# Decoder.net
KiCad netlist of a schematic drawn in EAGLE
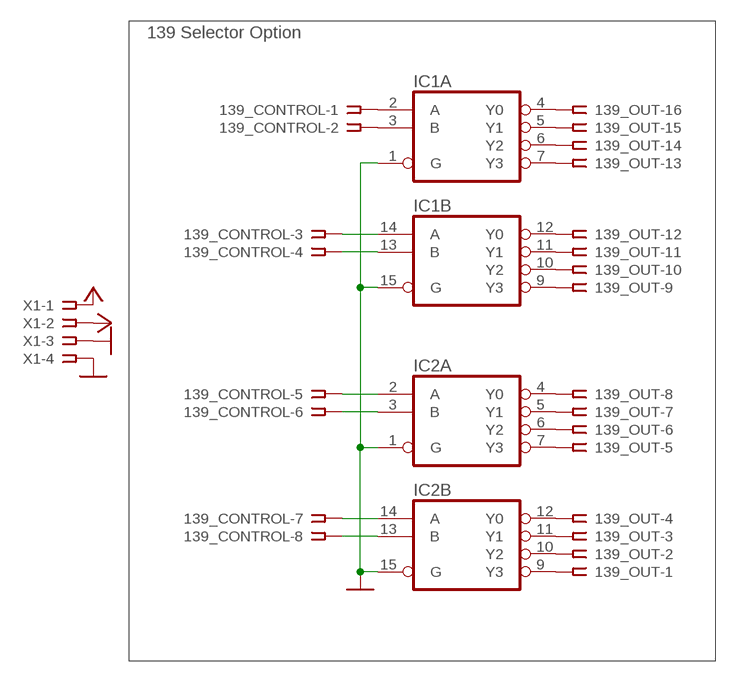
[diagram p0: schematic, sheet 1]

(export (version "E")
  (design (tool "Eeschema 10.0.6"))
  (components
    (comp (ref "139_CONTROL")
      (value "SSW-108-02-G-S")
      (footprint "eagle-import:SSW-108-02-G-S")
      (fields (field (name "MF") "Samtec Inc."))
      (libsource (lib "eagle-import") (part "SSW-108-02-G-S"))
    )
    (comp (ref "139_OUT")
      (value "SSW-116-02-G-S")
      (footprint "eagle-import:SSW-116-02-G-S")
      (fields (field (name "MF") "Samtec Inc."))
      (libsource (lib "eagle-import") (part "SSW-116-02-G-S"))
    )
    (comp (ref "IC1")
      (value "74AC139N")
      (footprint "eagle-import:DIL16")
      (libsource (lib "eagle-import") (part "74139NAC"))
    )
    (comp (ref "IC2")
      (value "74AC139N")
      (footprint "eagle-import:DIL16")
      (libsource (lib "eagle-import") (part "74139NAC"))
    )
    (comp (ref "X1")
      (value "SSW-104-02-G-S")
      (footprint "eagle-import:SSW-104-02-G-S")
      (fields (field (name "MF") "Samtec Inc."))
      (libsource (lib "eagle-import") (part "SSW-104-02-G-S"))
    )
  )
  (nets
    (net (code "1") (name "GND") (class "Default")
      (node (ref "IC1") (pin "1") (pinfunction "G_1") (pintype "input"))
      (node (ref "IC1") (pin "15") (pinfunction "G_15") (pintype "input"))
      (node (ref "IC2") (pin "1") (pinfunction "G_1") (pintype "input"))
      (node (ref "IC2") (pin "15") (pinfunction "G_15") (pintype "input"))
      (node (ref "X1") (pin "3") (pinfunction "1_3") (pintype "passive"))
      (node (ref "X1") (pin "4") (pinfunction "1_4") (pintype "passive"))
    )
    (net (code "2") (name "Net-(139_CONTROLB-1)") (class "Default")
      (node (ref "139_CONTROL") (pin "2") (pinfunction "1_2") (pintype "passive"))
      (node (ref "IC1") (pin "3") (pinfunction "B_3") (pintype "input"))
    )
    (net (code "3") (name "Net-(139_CONTROLC-1)") (class "Default")
      (node (ref "139_CONTROL") (pin "3") (pinfunction "1_3") (pintype "passive"))
      (node (ref "IC1") (pin "14") (pinfunction "A_14") (pintype "input"))
    )
    (net (code "4") (name "Net-(139_CONTROLD-1)") (class "Default")
      (node (ref "139_CONTROL") (pin "4") (pinfunction "1_4") (pintype "passive"))
      (node (ref "IC1") (pin "13") (pinfunction "B_13") (pintype "input"))
    )
    (net (code "5") (name "Net-(139_CONTROLE-1)") (class "Default")
      (node (ref "139_CONTROL") (pin "5") (pinfunction "1_5") (pintype "passive"))
      (node (ref "IC2") (pin "2") (pinfunction "A_2") (pintype "input"))
    )
    (net (code "6") (name "Net-(139_CONTROLF-1)") (class "Default")
      (node (ref "139_CONTROL") (pin "6") (pinfunction "1_6") (pintype "passive"))
      (node (ref "IC2") (pin "3") (pinfunction "B_3") (pintype "input"))
    )
    (net (code "7") (name "Net-(139_CONTROLG-1)") (class "Default")
      (node (ref "139_CONTROL") (pin "7") (pinfunction "1_7") (pintype "passive"))
      (node (ref "IC2") (pin "14") (pinfunction "A_14") (pintype "input"))
    )
    (net (code "8") (name "Net-(139_CONTROLH-1)") (class "Default")
      (node (ref "139_CONTROL") (pin "8") (pinfunction "1_8") (pintype "passive"))
      (node (ref "IC2") (pin "13") (pinfunction "B_13") (pintype "input"))
    )
    (net (code "9") (name "Net-(139_OUTB-1)") (class "Default")
      (node (ref "139_OUT") (pin "10") (pinfunction "1_10") (pintype "passive"))
      (node (ref "IC1") (pin "10") (pinfunction "Y2_10") (pintype "output"))
    )
    (net (code "10") (name "Net-(139_OUTC-1)") (class "Default")
      (node (ref "139_OUT") (pin "11") (pinfunction "1_11") (pintype "passive"))
      (node (ref "IC1") (pin "11") (pinfunction "Y1_11") (pintype "output"))
    )
    (net (code "11") (name "Net-(139_OUTD-1)") (class "Default")
      (node (ref "139_OUT") (pin "12") (pinfunction "1_12") (pintype "passive"))
      (node (ref "IC1") (pin "12") (pinfunction "Y0_12") (pintype "output"))
    )
    (net (code "12") (name "Net-(139_OUTE-1)") (class "Default")
      (node (ref "139_OUT") (pin "13") (pinfunction "1_13") (pintype "passive"))
      (node (ref "IC1") (pin "7") (pinfunction "Y3_7") (pintype "output"))
    )
    (net (code "13") (name "Net-(139_OUTF-1)") (class "Default")
      (node (ref "139_OUT") (pin "14") (pinfunction "1_14") (pintype "passive"))
      (node (ref "IC1") (pin "6") (pinfunction "Y2_6") (pintype "output"))
    )
    (net (code "14") (name "Net-(139_OUTG-1)") (class "Default")
      (node (ref "139_OUT") (pin "15") (pinfunction "1_15") (pintype "passive"))
      (node (ref "IC1") (pin "5") (pinfunction "Y1_5") (pintype "output"))
    )
    (net (code "15") (name "Net-(139_OUTH-1)") (class "Default")
      (node (ref "139_OUT") (pin "16") (pinfunction "1_16") (pintype "passive"))
      (node (ref "IC1") (pin "4") (pinfunction "Y0_4") (pintype "output"))
    )
    (net (code "16") (name "Net-(139_OUTI-1)") (class "Default")
      (node (ref "139_OUT") (pin "2") (pinfunction "1_2") (pintype "passive"))
      (node (ref "IC2") (pin "10") (pinfunction "Y2_10") (pintype "output"))
    )
    (net (code "17") (name "Net-(139_OUTJ-1)") (class "Default")
      (node (ref "139_OUT") (pin "3") (pinfunction "1_3") (pintype "passive"))
      (node (ref "IC2") (pin "11") (pinfunction "Y1_11") (pintype "output"))
    )
    (net (code "18") (name "Net-(139_OUTK-1)") (class "Default")
      (node (ref "139_OUT") (pin "4") (pinfunction "1_4") (pintype "passive"))
      (node (ref "IC2") (pin "12") (pinfunction "Y0_12") (pintype "output"))
    )
    (net (code "19") (name "Net-(139_OUTL-1)") (class "Default")
      (node (ref "139_OUT") (pin "5") (pinfunction "1_5") (pintype "passive"))
      (node (ref "IC2") (pin "7") (pinfunction "Y3_7") (pintype "output"))
    )
    (net (code "20") (name "Net-(139_OUTM-1)") (class "Default")
      (node (ref "139_OUT") (pin "6") (pinfunction "1_6") (pintype "passive"))
      (node (ref "IC2") (pin "6") (pinfunction "Y2_6") (pintype "output"))
    )
    (net (code "21") (name "Net-(139_OUTN-1)") (class "Default")
      (node (ref "139_OUT") (pin "7") (pinfunction "1_7") (pintype "passive"))
      (node (ref "IC2") (pin "5") (pinfunction "Y1_5") (pintype "output"))
    )
    (net (code "22") (name "Net-(139_OUTO-1)") (class "Default")
      (node (ref "139_OUT") (pin "8") (pinfunction "1_8") (pintype "passive"))
      (node (ref "IC2") (pin "4") (pinfunction "Y0_4") (pintype "output"))
    )
    (net (code "23") (name "Net-(139_OUTP-1)") (class "Default")
      (node (ref "139_OUT") (pin "9") (pinfunction "1_9") (pintype "passive"))
      (node (ref "IC1") (pin "9") (pinfunction "Y3_9") (pintype "output"))
    )
    (net (code "24") (name "Net-(IC1A-A)") (class "Default")
      (node (ref "139_CONTROL") (pin "1") (pinfunction "1_1") (pintype "passive"))
      (node (ref "IC1") (pin "2") (pinfunction "A_2") (pintype "input"))
    )
    (net (code "25") (name "Net-(IC2B-Y3)") (class "Default")
      (node (ref "139_OUT") (pin "1") (pinfunction "1_1") (pintype "passive"))
      (node (ref "IC2") (pin "9") (pinfunction "Y3_9") (pintype "output"))
    )
    (net (code "26") (name "VCC") (class "Default")
      (node (ref "X1") (pin "1") (pinfunction "1_1") (pintype "passive"))
      (node (ref "X1") (pin "2") (pinfunction "1_2") (pintype "passive"))
    )
  )
)
